# ComponentTester-rev_1.net
KiCad netlist of a schematic drawn in EAGLE
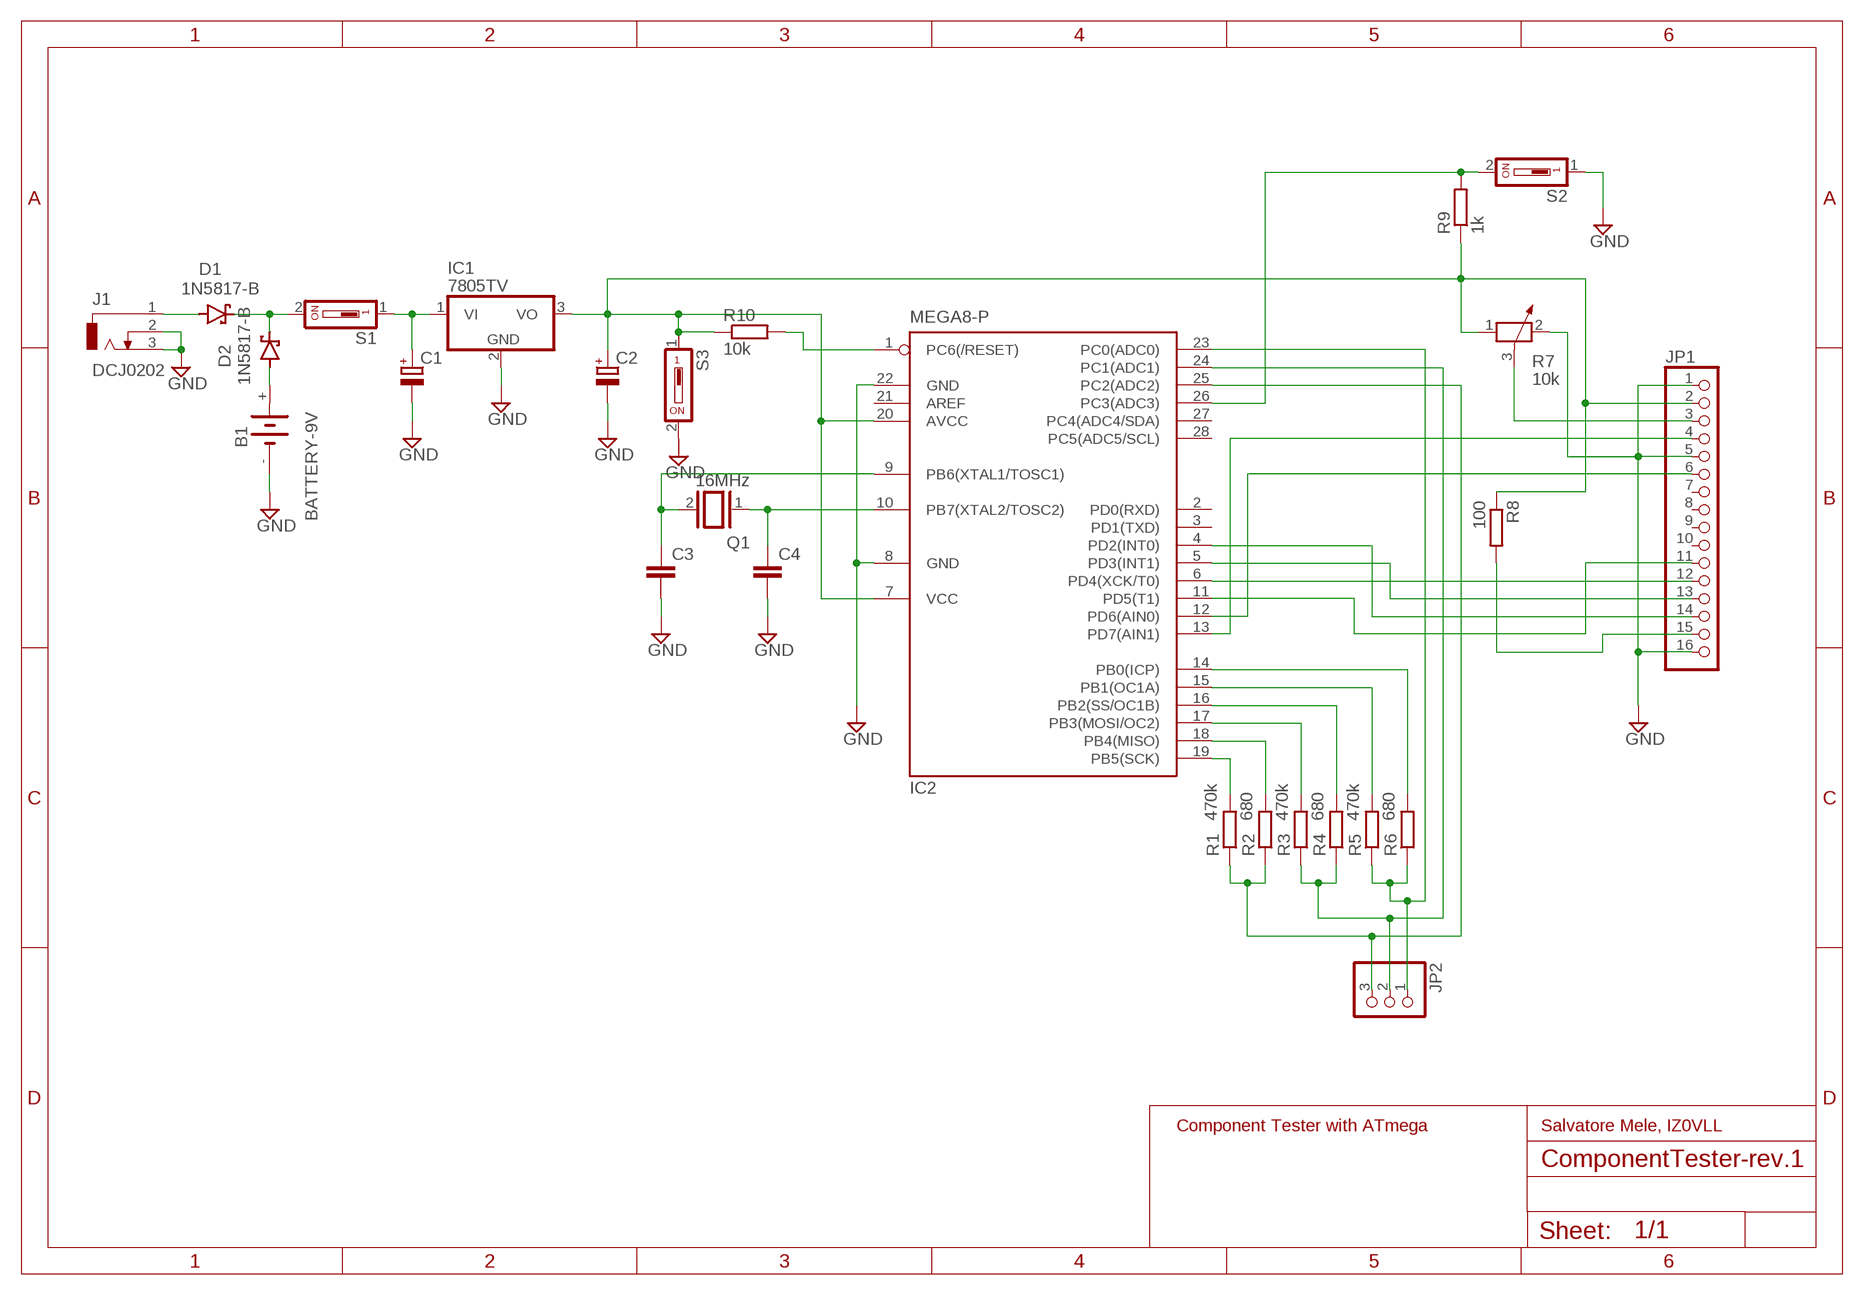
[diagram p0: schematic, sheet 1]

(export (version "E")
  (design (tool "Eeschema 10.0.6"))
  (components
    (comp (ref "B1")
      (value "BATTERY-9V")
      (footprint "eagle-import:9V-BATTERY-SNAP")
      (libsource (lib "eagle-import") (part "BATTERY-9V"))
    )
    (comp (ref "C1")
      (value "CPOL-EUE2.5-6")
      (footprint "eagle-import:E2,5-6")
      (libsource (lib "eagle-import") (part "CPOL-EUE2.5-6"))
    )
    (comp (ref "C2")
      (value "CPOL-EUE2.5-6")
      (footprint "eagle-import:E2,5-6")
      (libsource (lib "eagle-import") (part "CPOL-EUE2.5-6"))
    )
    (comp (ref "C3")
      (value "C-EU025-024X044")
      (footprint "eagle-import:C025-024X044")
      (libsource (lib "eagle-import") (part "C-EU025-024X044"))
    )
    (comp (ref "C4")
      (value "C-EU025-024X044")
      (footprint "eagle-import:C025-024X044")
      (libsource (lib "eagle-import") (part "C-EU025-024X044"))
    )
    (comp (ref "D1")
      (value "1N5817-B")
      (footprint "eagle-import:DO41-7.6")
      (libsource (lib "eagle-import") (part "1N5817-B"))
    )
    (comp (ref "D2")
      (value "1N5817-B")
      (footprint "eagle-import:DO41-7.6")
      (libsource (lib "eagle-import") (part "1N5817-B"))
    )
    (comp (ref "IC1")
      (value "7805TV")
      (footprint "eagle-import:TO220V")
      (libsource (lib "eagle-import") (part "78TV05"))
    )
    (comp (ref "IC2")
      (value "MEGA8-P")
      (footprint "eagle-import:DIL28-3")
      (libsource (lib "eagle-import") (part "MEGA8-P"))
    )
    (comp (ref "J1")
      (value "DCJ0202")
      (footprint "eagle-import:DCJ0202")
      (libsource (lib "eagle-import") (part "DCJ0202"))
    )
    (comp (ref "JP1")
      (value "PINHD-1X16")
      (footprint "eagle-import:1X16")
      (libsource (lib "eagle-import") (part "PINHD-1X16"))
    )
    (comp (ref "JP2")
      (value "PINHD-1X3")
      (footprint "eagle-import:1X03")
      (libsource (lib "eagle-import") (part "PINHD-1X3"))
    )
    (comp (ref "Q1")
      (value "16MHz")
      (footprint "eagle-import:QS")
      (libsource (lib "eagle-import") (part "XTAL/S"))
    )
    (comp (ref "R1")
      (value "470k")
      (footprint "eagle-import:0207_10")
      (libsource (lib "eagle-import") (part "R-EU_0207/10"))
    )
    (comp (ref "R2")
      (value "680")
      (footprint "eagle-import:0207_10")
      (libsource (lib "eagle-import") (part "R-EU_0207/10"))
    )
    (comp (ref "R3")
      (value "470k")
      (footprint "eagle-import:0207_10")
      (libsource (lib "eagle-import") (part "R-EU_0207/10"))
    )
    (comp (ref "R4")
      (value "680")
      (footprint "eagle-import:0207_10")
      (libsource (lib "eagle-import") (part "R-EU_0207/10"))
    )
    (comp (ref "R5")
      (value "470k")
      (footprint "eagle-import:0207_10")
      (libsource (lib "eagle-import") (part "R-EU_0207/10"))
    )
    (comp (ref "R6")
      (value "680")
      (footprint "eagle-import:0207_10")
      (libsource (lib "eagle-import") (part "R-EU_0207/10"))
    )
    (comp (ref "R7")
      (value "10k")
      (footprint "eagle-import:PT-10S")
      (libsource (lib "eagle-import") (part "POTENTIOMETER_PT-10S"))
    )
    (comp (ref "R8")
      (value "100")
      (footprint "eagle-import:0207_10")
      (libsource (lib "eagle-import") (part "R-EU_0207/10"))
    )
    (comp (ref "R9")
      (value "1k")
      (footprint "eagle-import:0207_10")
      (libsource (lib "eagle-import") (part "R-EU_0207/10"))
    )
    (comp (ref "R10")
      (value "10k")
      (footprint "eagle-import:0207_10")
      (libsource (lib "eagle-import") (part "R-EU_0207/10"))
    )
    (comp (ref "S1")
      (value "SD4-01")
      (footprint "eagle-import:SD4-01")
      (libsource (lib "eagle-import") (part "SD4-01"))
    )
    (comp (ref "S2")
      (value "SD4-01")
      (footprint "eagle-import:SD4-01")
      (libsource (lib "eagle-import") (part "SD4-01"))
    )
    (comp (ref "S3")
      (value "SD4-01")
      (footprint "eagle-import:SD4-01")
      (libsource (lib "eagle-import") (part "SD4-01"))
    )
  )
  (nets
    (net (code "1") (name "GND") (class "Default")
      (node (ref "B1") (pin "-") (pinfunction "-_-") (pintype "passive"))
      (node (ref "C1") (pin "-") (pinfunction "-_-") (pintype "passive"))
      (node (ref "C2") (pin "-") (pinfunction "-_-") (pintype "passive"))
      (node (ref "C3") (pin "2") (pinfunction "2_2") (pintype "passive"))
      (node (ref "C4") (pin "2") (pinfunction "2_2") (pintype "passive"))
      (node (ref "IC1") (pin "2") (pinfunction "GND_2") (pintype "passive"))
      (node (ref "IC2") (pin "22") (pinfunction "GND_22") (pintype "power_in"))
      (node (ref "IC2") (pin "8") (pinfunction "GND_8") (pintype "power_in"))
      (node (ref "J1") (pin "2") (pinfunction "2_2") (pintype "passive"))
      (node (ref "J1") (pin "3") (pinfunction "3_3") (pintype "passive"))
      (node (ref "JP1") (pin "1") (pinfunction "1_1") (pintype "passive"))
      (node (ref "JP1") (pin "16") (pinfunction "16_16") (pintype "passive"))
      (node (ref "JP1") (pin "5") (pinfunction "5_5") (pintype "passive"))
      (node (ref "R7") (pin "2") (pinfunction "2_2") (pintype "passive"))
      (node (ref "S2") (pin "1") (pinfunction "1_1") (pintype "passive"))
      (node (ref "S3") (pin "2") (pinfunction "2_2") (pintype "passive"))
    )
    (net (code "2") (name "Net-(B1-Pad+)") (class "Default")
      (node (ref "B1") (pin "+") (pinfunction "+_+") (pintype "passive"))
      (node (ref "D2") (pin "A") (pinfunction "A_A") (pintype "passive"))
    )
    (net (code "3") (name "Net-(D1-PadA)") (class "Default")
      (node (ref "D1") (pin "A") (pinfunction "A_A") (pintype "passive"))
      (node (ref "J1") (pin "1") (pinfunction "1_1") (pintype "passive"))
    )
    (net (code "4") (name "Net-(D1-PadC)") (class "Default")
      (node (ref "D1") (pin "C") (pinfunction "C_C") (pintype "passive"))
      (node (ref "D2") (pin "C") (pinfunction "C_C") (pintype "passive"))
      (node (ref "S1") (pin "2") (pinfunction "2_2") (pintype "passive"))
    )
    (net (code "5") (name "Net-(IC1-VI)") (class "Default")
      (node (ref "C1") (pin "+") (pinfunction "+_+") (pintype "passive"))
      (node (ref "IC1") (pin "1") (pinfunction "VI_1") (pintype "input"))
      (node (ref "S1") (pin "1") (pinfunction "1_1") (pintype "passive"))
    )
    (net (code "6") (name "Net-(IC1-VO)") (class "Default")
      (node (ref "C2") (pin "+") (pinfunction "+_+") (pintype "passive"))
      (node (ref "IC1") (pin "3") (pinfunction "VO_3") (pintype "passive"))
      (node (ref "IC2") (pin "20") (pinfunction "AVCC_20") (pintype "power_in"))
      (node (ref "IC2") (pin "7") (pinfunction "VCC_7") (pintype "power_in"))
      (node (ref "JP1") (pin "2") (pinfunction "2_2") (pintype "passive"))
      (node (ref "R10") (pin "1") (pinfunction "1_1") (pintype "passive"))
      (node (ref "R7") (pin "1") (pinfunction "1_1") (pintype "passive"))
      (node (ref "R8") (pin "1") (pinfunction "1_1") (pintype "passive"))
      (node (ref "R9") (pin "1") (pinfunction "1_1") (pintype "passive"))
      (node (ref "S3") (pin "1") (pinfunction "1_1") (pintype "passive"))
    )
    (net (code "7") (name "Net-(IC2-PB0(ICP))") (class "Default")
      (node (ref "IC2") (pin "14") (pinfunction "PB0(ICP)_14") (pintype "bidirectional"))
      (node (ref "R6") (pin "2") (pinfunction "2_2") (pintype "passive"))
    )
    (net (code "8") (name "Net-(IC2-PB1(OC1A))") (class "Default")
      (node (ref "IC2") (pin "15") (pinfunction "PB1(OC1A)_15") (pintype "bidirectional"))
      (node (ref "R5") (pin "2") (pinfunction "2_2") (pintype "passive"))
    )
    (net (code "9") (name "Net-(IC2-PB2(SS{slash}OC1B))") (class "Default")
      (node (ref "IC2") (pin "16") (pinfunction "PB2(SS/OC1B)_16") (pintype "bidirectional"))
      (node (ref "R4") (pin "2") (pinfunction "2_2") (pintype "passive"))
    )
    (net (code "10") (name "Net-(IC2-PB3(MOSI{slash}OC2))") (class "Default")
      (node (ref "IC2") (pin "17") (pinfunction "PB3(MOSI/OC2)_17") (pintype "bidirectional"))
      (node (ref "R3") (pin "2") (pinfunction "2_2") (pintype "passive"))
    )
    (net (code "11") (name "Net-(IC2-PB4(MISO))") (class "Default")
      (node (ref "IC2") (pin "18") (pinfunction "PB4(MISO)_18") (pintype "bidirectional"))
      (node (ref "R2") (pin "2") (pinfunction "2_2") (pintype "passive"))
    )
    (net (code "12") (name "Net-(IC2-PB5(SCK))") (class "Default")
      (node (ref "IC2") (pin "19") (pinfunction "PB5(SCK)_19") (pintype "bidirectional"))
      (node (ref "R1") (pin "2") (pinfunction "2_2") (pintype "passive"))
    )
    (net (code "13") (name "Net-(IC2-PB6(XTAL1{slash}TOSC1))") (class "Default")
      (node (ref "C3") (pin "1") (pinfunction "1_1") (pintype "passive"))
      (node (ref "IC2") (pin "9") (pinfunction "PB6(XTAL1/TOSC1)_9") (pintype "bidirectional"))
      (node (ref "Q1") (pin "2") (pinfunction "2_2") (pintype "passive"))
    )
    (net (code "14") (name "Net-(IC2-PB7(XTAL2{slash}TOSC2))") (class "Default")
      (node (ref "C4") (pin "1") (pinfunction "1_1") (pintype "passive"))
      (node (ref "IC2") (pin "10") (pinfunction "PB7(XTAL2/TOSC2)_10") (pintype "bidirectional"))
      (node (ref "Q1") (pin "1") (pinfunction "1_1") (pintype "passive"))
    )
    (net (code "15") (name "Net-(IC2-PC0(ADC0))") (class "Default")
      (node (ref "IC2") (pin "23") (pinfunction "PC0(ADC0)_23") (pintype "bidirectional"))
      (node (ref "JP2") (pin "1") (pinfunction "1_1") (pintype "passive"))
      (node (ref "R5") (pin "1") (pinfunction "1_1") (pintype "passive"))
      (node (ref "R6") (pin "1") (pinfunction "1_1") (pintype "passive"))
    )
    (net (code "16") (name "Net-(IC2-PC1(ADC1))") (class "Default")
      (node (ref "IC2") (pin "24") (pinfunction "PC1(ADC1)_24") (pintype "bidirectional"))
      (node (ref "JP2") (pin "2") (pinfunction "2_2") (pintype "passive"))
      (node (ref "R3") (pin "1") (pinfunction "1_1") (pintype "passive"))
      (node (ref "R4") (pin "1") (pinfunction "1_1") (pintype "passive"))
    )
    (net (code "17") (name "Net-(IC2-PC2(ADC2))") (class "Default")
      (node (ref "IC2") (pin "25") (pinfunction "PC2(ADC2)_25") (pintype "bidirectional"))
      (node (ref "JP2") (pin "3") (pinfunction "3_3") (pintype "passive"))
      (node (ref "R1") (pin "1") (pinfunction "1_1") (pintype "passive"))
      (node (ref "R2") (pin "1") (pinfunction "1_1") (pintype "passive"))
    )
    (net (code "18") (name "Net-(IC2-PC3(ADC3))") (class "Default")
      (node (ref "IC2") (pin "26") (pinfunction "PC3(ADC3)_26") (pintype "bidirectional"))
      (node (ref "R9") (pin "2") (pinfunction "2_2") (pintype "passive"))
      (node (ref "S2") (pin "2") (pinfunction "2_2") (pintype "passive"))
    )
    (net (code "19") (name "Net-(IC2-PC6({slash}RESET))") (class "Default")
      (node (ref "IC2") (pin "1") (pinfunction "PC6(/RESET)_1") (pintype "bidirectional"))
      (node (ref "R10") (pin "2") (pinfunction "2_2") (pintype "passive"))
    )
    (net (code "20") (name "Net-(IC2-PD2(INT0))") (class "Default")
      (node (ref "IC2") (pin "4") (pinfunction "PD2(INT0)_4") (pintype "bidirectional"))
      (node (ref "JP1") (pin "14") (pinfunction "14_14") (pintype "passive"))
    )
    (net (code "21") (name "Net-(IC2-PD3(INT1))") (class "Default")
      (node (ref "IC2") (pin "5") (pinfunction "PD3(INT1)_5") (pintype "bidirectional"))
      (node (ref "JP1") (pin "13") (pinfunction "13_13") (pintype "passive"))
    )
    (net (code "22") (name "Net-(IC2-PD4(XCK{slash}T0))") (class "Default")
      (node (ref "IC2") (pin "6") (pinfunction "PD4(XCK/T0)_6") (pintype "bidirectional"))
      (node (ref "JP1") (pin "12") (pinfunction "12_12") (pintype "passive"))
    )
    (net (code "23") (name "Net-(IC2-PD5(T1))") (class "Default")
      (node (ref "IC2") (pin "11") (pinfunction "PD5(T1)_11") (pintype "bidirectional"))
      (node (ref "JP1") (pin "11") (pinfunction "11_11") (pintype "passive"))
    )
    (net (code "24") (name "Net-(IC2-PD6(AIN0))") (class "Default")
      (node (ref "IC2") (pin "12") (pinfunction "PD6(AIN0)_12") (pintype "bidirectional"))
      (node (ref "JP1") (pin "6") (pinfunction "6_6") (pintype "passive"))
    )
    (net (code "25") (name "Net-(IC2-PD7(AIN1))") (class "Default")
      (node (ref "IC2") (pin "13") (pinfunction "PD7(AIN1)_13") (pintype "bidirectional"))
      (node (ref "JP1") (pin "4") (pinfunction "4_4") (pintype "passive"))
    )
    (net (code "26") (name "Net-(JP1-Pad3)") (class "Default")
      (node (ref "JP1") (pin "3") (pinfunction "3_3") (pintype "passive"))
      (node (ref "R7") (pin "3") (pinfunction "3_3") (pintype "passive"))
    )
    (net (code "27") (name "Net-(JP1-Pad15)") (class "Default")
      (node (ref "JP1") (pin "15") (pinfunction "15_15") (pintype "passive"))
      (node (ref "R8") (pin "2") (pinfunction "2_2") (pintype "passive"))
    )
    (net (code "28") (name "unconnected-(IC2-AREF-Pad21)") (class "Default")
      (node (ref "IC2") (pin "21") (pinfunction "AREF_21") (pintype "passive"))
    )
    (net (code "29") (name "unconnected-(IC2-PC4(ADC4{slash}SDA)-Pad27)") (class "Default")
      (node (ref "IC2") (pin "27") (pinfunction "PC4(ADC4/SDA)_27") (pintype "bidirectional"))
    )
    (net (code "30") (name "unconnected-(IC2-PC5(ADC5{slash}SCL)-Pad28)") (class "Default")
      (node (ref "IC2") (pin "28") (pinfunction "PC5(ADC5/SCL)_28") (pintype "bidirectional"))
    )
    (net (code "31") (name "unconnected-(IC2-PD0(RXD)-Pad2)") (class "Default")
      (node (ref "IC2") (pin "2") (pinfunction "PD0(RXD)_2") (pintype "bidirectional"))
    )
    (net (code "32") (name "unconnected-(IC2-PD1(TXD)-Pad3)") (class "Default")
      (node (ref "IC2") (pin "3") (pinfunction "PD1(TXD)_3") (pintype "bidirectional"))
    )
    (net (code "33") (name "unconnected-(JP1-Pad7)") (class "Default")
      (node (ref "JP1") (pin "7") (pinfunction "7_7") (pintype "passive"))
    )
    (net (code "34") (name "unconnected-(JP1-Pad8)") (class "Default")
      (node (ref "JP1") (pin "8") (pinfunction "8_8") (pintype "passive"))
    )
    (net (code "35") (name "unconnected-(JP1-Pad9)") (class "Default")
      (node (ref "JP1") (pin "9") (pinfunction "9_9") (pintype "passive"))
    )
    (net (code "36") (name "unconnected-(JP1-Pad10)") (class "Default")
      (node (ref "JP1") (pin "10") (pinfunction "10_10") (pintype "passive"))
    )
  )
)
